# buckConverterRev3schematic.net
KiCad netlist of a schematic drawn in EAGLE
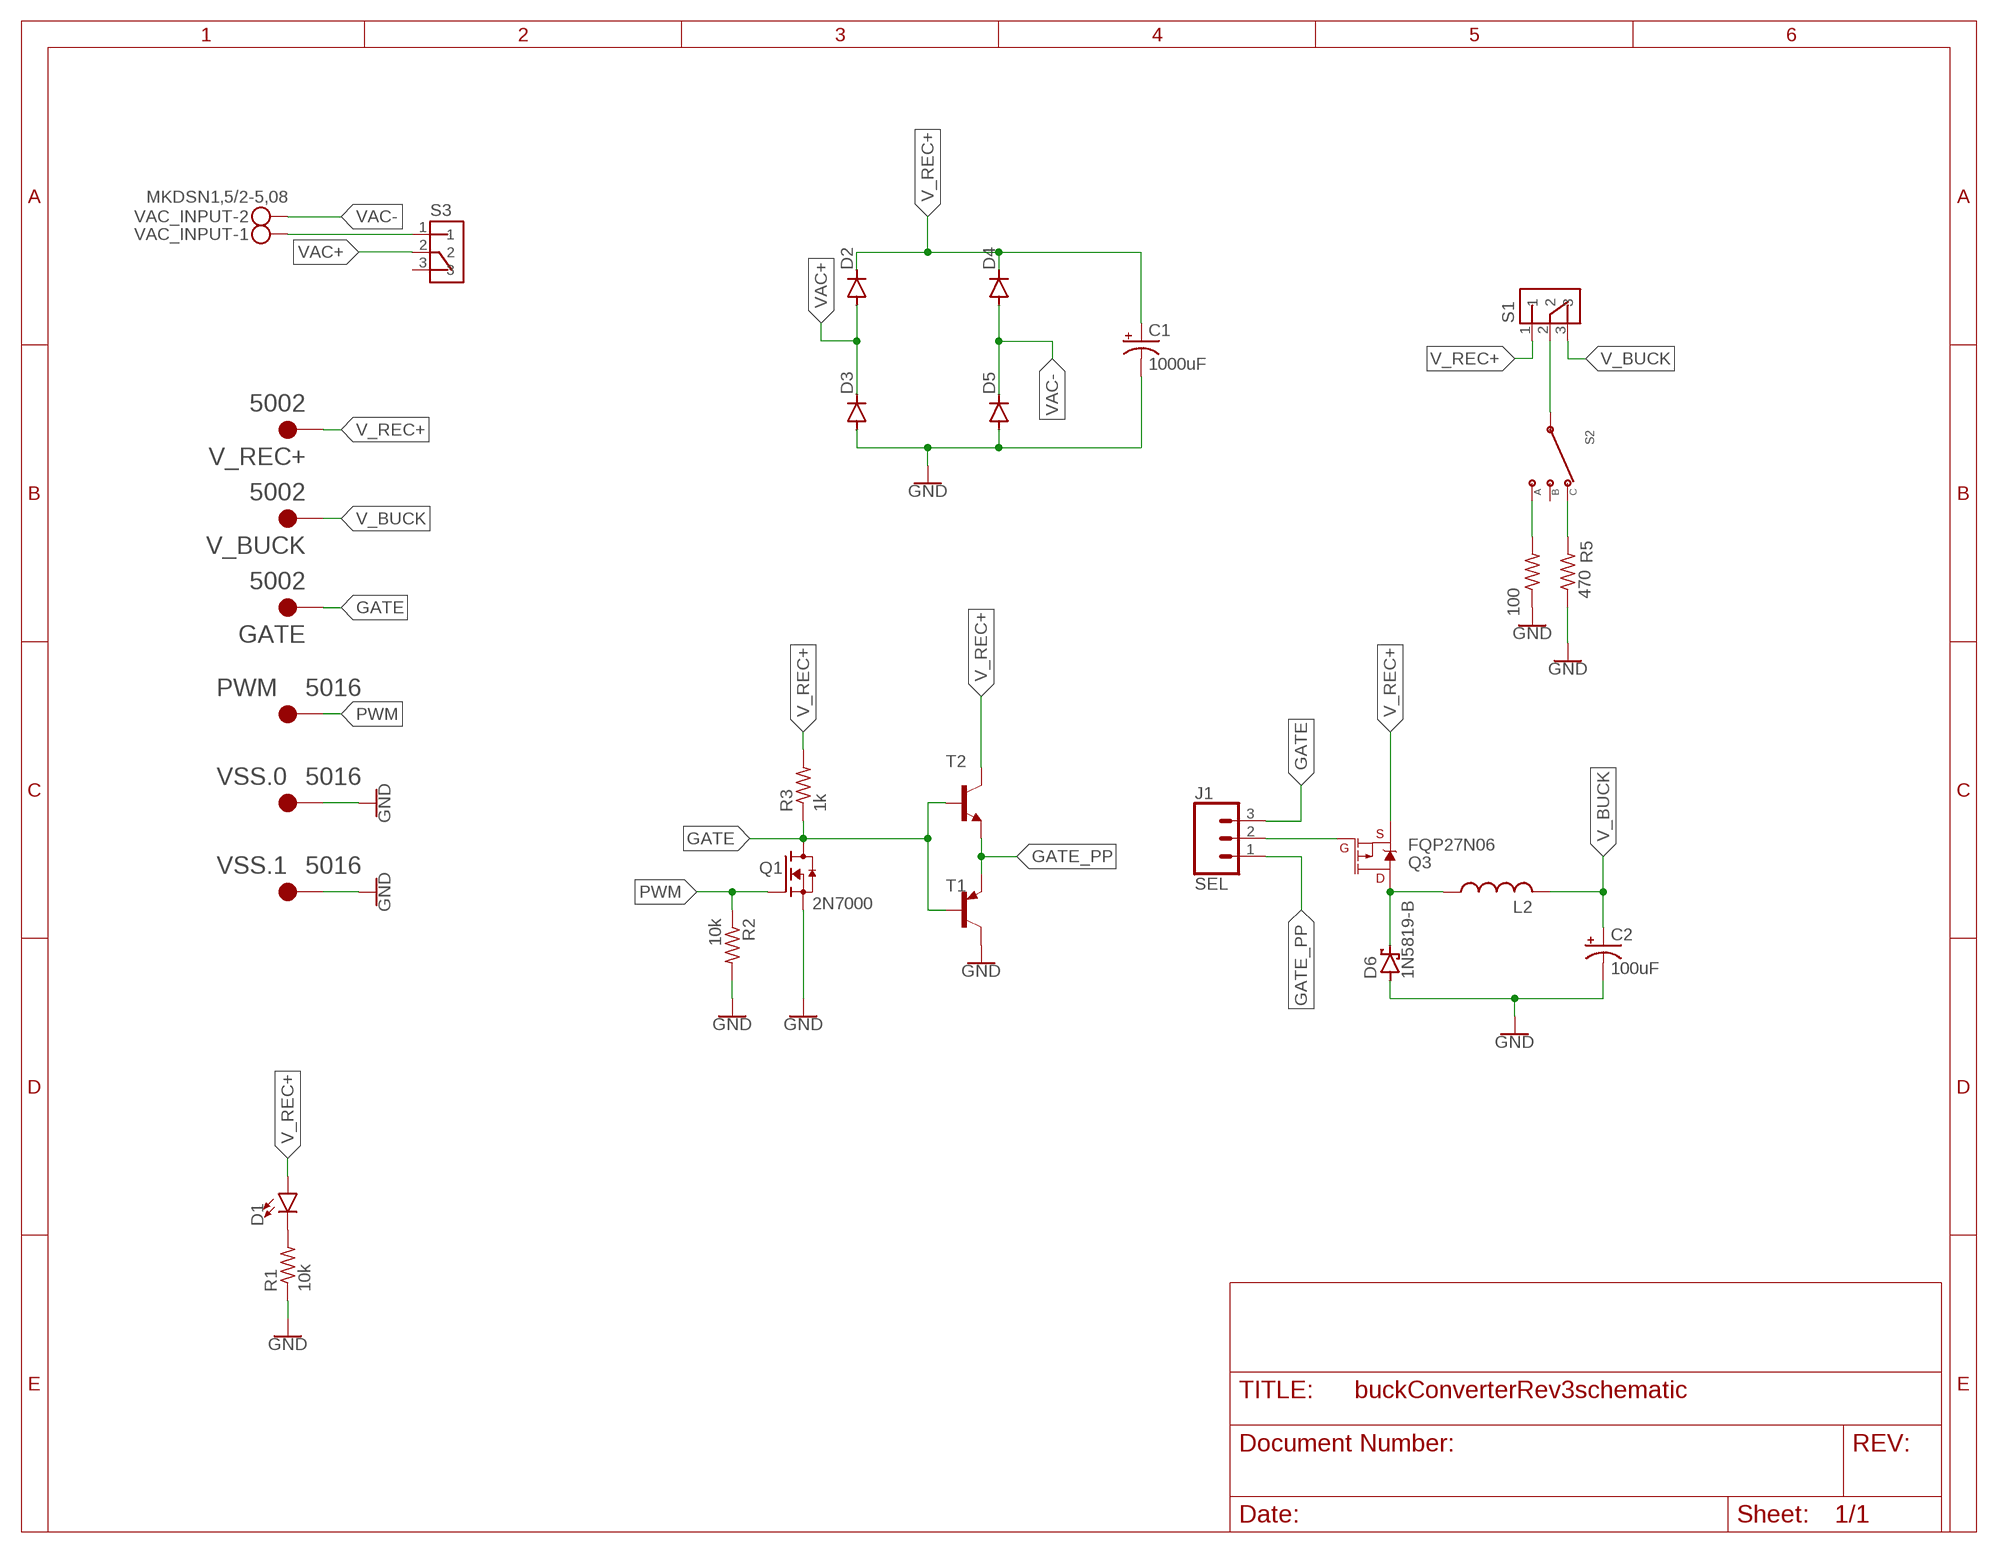
[diagram p0: schematic, sheet 1]

(export (version "E")
  (design (tool "Eeschema 10.0.6"))
  (components
    (comp (ref "C1")
      (value "1000uF")
      (footprint "eagle-import:SANYO-OSCON_F13")
      (libsource (lib "eagle-import") (part "CPOL-USSANYO_F13"))
    )
    (comp (ref "C2")
      (value "100uF")
      (footprint "eagle-import:SANYO-OSCON_C")
      (libsource (lib "eagle-import") (part "CPOL-USSANYO_C"))
    )
    (comp (ref "D1")
      (value "LED5MM")
      (footprint "eagle-import:LED_5MM")
      (libsource (lib "eagle-import") (part "LED5MM"))
    )
    (comp (ref "D2")
      (value "DIODE-DO41-7.6")
      (footprint "eagle-import:DO41-7.6")
      (libsource (lib "eagle-import") (part "DIODE-DO41-7.6"))
    )
    (comp (ref "D3")
      (value "DIODE-DO41-7.6")
      (footprint "eagle-import:DO41-7.6")
      (libsource (lib "eagle-import") (part "DIODE-DO41-7.6"))
    )
    (comp (ref "D4")
      (value "DIODE-DO41-7.6")
      (footprint "eagle-import:DO41-7.6")
      (libsource (lib "eagle-import") (part "DIODE-DO41-7.6"))
    )
    (comp (ref "D5")
      (value "DIODE-DO41-7.6")
      (footprint "eagle-import:DO41-7.6")
      (libsource (lib "eagle-import") (part "DIODE-DO41-7.6"))
    )
    (comp (ref "D6")
      (value "1N5819-B")
      (footprint "eagle-import:DO41-7.6")
      (libsource (lib "eagle-import") (part "1N5819-B"))
    )
    (comp (ref "GATE")
      (value "5002")
      (footprint "eagle-import:KEYSTONE_5002")
      (fields (field (name "MANUFACTURER") "Keystone"))
      (libsource (lib "eagle-import") (part "5002"))
    )
    (comp (ref "J1")
      (value "SEL")
      (footprint "eagle-import:1X03_LOCK_LONGPADS")
      (libsource (lib "eagle-import") (part "CONN_03LOCK_LONGPADS"))
    )
    (comp (ref "L2")
      (value "L-US6000-XXX-RC")
      (footprint "eagle-import:6000-XXXX-RC")
      (libsource (lib "eagle-import") (part "L-US6000-XXX-RC"))
    )
    (comp (ref "PWM")
      (value "5016")
      (footprint "eagle-import:KEYSTONE_5016")
      (fields (field (name "MANUFACTURER") "Keystone Electronics"))
      (libsource (lib "eagle-import") (part "5016"))
    )
    (comp (ref "Q1")
      (value "2N7000")
      (footprint "eagle-import:TO92254P458H750-3")
      (fields (field (name "MANUFACTURER") "Diotec Semiconductor"))
      (libsource (lib "eagle-import") (part "2N7000"))
    )
    (comp (ref "Q3")
      (value "FQP27N06")
      (footprint "eagle-import:TO220V")
      (libsource (lib "eagle-import") (part "MOSFET_PCH-NDP6020P"))
    )
    (comp (ref "R1")
      (value "10k")
      (footprint "eagle-import:0207_10")
      (libsource (lib "eagle-import") (part "R-US_0207/10"))
    )
    (comp (ref "R2")
      (value "10k")
      (footprint "eagle-import:0207_10")
      (libsource (lib "eagle-import") (part "R-US_0207/10"))
    )
    (comp (ref "R3")
      (value "1k")
      (footprint "eagle-import:0207_10")
      (libsource (lib "eagle-import") (part "R-US_0207/10"))
    )
    (comp (ref "R4")
      (value "100")
      (footprint "eagle-import:0617_22")
      (libsource (lib "eagle-import") (part "R-US_0617/22"))
    )
    (comp (ref "R5")
      (value "470")
      (footprint "eagle-import:0309_12")
      (libsource (lib "eagle-import") (part "R-US_0309/12"))
    )
    (comp (ref "S1")
      (value "OS102011MS2QN1")
      (footprint "eagle-import:SW_OS102011MS2QN1")
      (fields (field (name "MF") "C&K"))
      (libsource (lib "eagle-import") (part "OS102011MS2QN1"))
    )
    (comp (ref "S2")
      (value "OS103011MS8QP1")
      (footprint "eagle-import:OS102011MS8QP1")
      (fields (field (name "MF") "C&K"))
      (libsource (lib "eagle-import") (part "OS103011MS8QP1"))
    )
    (comp (ref "S3")
      (value "ON/OFF")
      (footprint "eagle-import:SW_OS102011MS2QN1")
      (fields (field (name "MF") "C&K") (field (name "MP") "OS102011MS2QN1"))
      (libsource (lib "eagle-import") (part "OS102011MS2QN1"))
    )
    (comp (ref "T1")
      (value "2N3906-PNP-TO92-EBC")
      (footprint "eagle-import:TO92-EBC")
      (libsource (lib "eagle-import") (part "-PNP-TO92-EBC2N3906"))
    )
    (comp (ref "T2")
      (value "2N3904-NPN-TO92-EBC")
      (footprint "eagle-import:TO92-EBC")
      (libsource (lib "eagle-import") (part "-NPN-TO92-EBC2N3904"))
    )
    (comp (ref "VAC_INPUT")
      (value "MKDSN1,5/2-5,08")
      (footprint "eagle-import:MKDSN1,5_2-5,08")
      (libsource (lib "eagle-import") (part "MKDSN1,5/2-5,08"))
    )
    (comp (ref "VSS.0")
      (value "5016")
      (footprint "eagle-import:KEYSTONE_5016")
      (fields (field (name "MANUFACTURER") "Keystone Electronics"))
      (libsource (lib "eagle-import") (part "5016"))
    )
    (comp (ref "VSS.1")
      (value "5016")
      (footprint "eagle-import:KEYSTONE_5016")
      (fields (field (name "MANUFACTURER") "Keystone Electronics"))
      (libsource (lib "eagle-import") (part "5016"))
    )
    (comp (ref "V_BUCK")
      (value "5002")
      (footprint "eagle-import:KEYSTONE_5002")
      (fields (field (name "MANUFACTURER") "Keystone"))
      (libsource (lib "eagle-import") (part "5002"))
    )
    (comp (ref "V_REC+")
      (value "5002")
      (footprint "eagle-import:KEYSTONE_5002")
      (fields (field (name "MANUFACTURER") "Keystone"))
      (libsource (lib "eagle-import") (part "5002"))
    )
  )
  (nets
    (net (code "1") (name "GATE") (class "Default")
      (node (ref "GATE") (pin "TP") (pinfunction "TP_TP") (pintype "passive"))
      (node (ref "J1") (pin "3") (pinfunction "3_3") (pintype "passive"))
      (node (ref "Q1") (pin "3") (pinfunction "D_3") (pintype "passive"))
      (node (ref "R3") (pin "1") (pinfunction "1_1") (pintype "passive"))
      (node (ref "T1") (pin "B") (pinfunction "B_B") (pintype "passive"))
      (node (ref "T2") (pin "B") (pinfunction "B_B") (pintype "passive"))
    )
    (net (code "2") (name "GATE_PP") (class "Default")
      (node (ref "J1") (pin "1") (pinfunction "1_1") (pintype "passive"))
      (node (ref "T1") (pin "E") (pinfunction "E_E") (pintype "passive"))
      (node (ref "T2") (pin "E") (pinfunction "E_E") (pintype "passive"))
    )
    (net (code "3") (name "GND") (class "Default")
      (node (ref "C1") (pin "-") (pinfunction "-_-") (pintype "passive"))
      (node (ref "C2") (pin "-") (pinfunction "-_-") (pintype "passive"))
      (node (ref "D3") (pin "A") (pinfunction "A_A") (pintype "passive"))
      (node (ref "D5") (pin "A") (pinfunction "A_A") (pintype "passive"))
      (node (ref "D6") (pin "A") (pinfunction "A_A") (pintype "passive"))
      (node (ref "Q1") (pin "1") (pinfunction "S_1") (pintype "passive"))
      (node (ref "R1") (pin "1") (pinfunction "1_1") (pintype "passive"))
      (node (ref "R2") (pin "2") (pinfunction "2_2") (pintype "passive"))
      (node (ref "R4") (pin "1") (pinfunction "1_1") (pintype "passive"))
      (node (ref "R5") (pin "1") (pinfunction "1_1") (pintype "passive"))
      (node (ref "T1") (pin "C") (pinfunction "C_C") (pintype "passive"))
      (node (ref "VSS.0") (pin "TP") (pinfunction "TP_TP") (pintype "passive"))
      (node (ref "VSS.1") (pin "TP") (pinfunction "TP_TP") (pintype "passive"))
    )
    (net (code "4") (name "Net-(D1-C)") (class "Default")
      (node (ref "D1") (pin "K") (pinfunction "C_K") (pintype "passive"))
      (node (ref "R1") (pin "2") (pinfunction "2_2") (pintype "passive"))
    )
    (net (code "5") (name "Net-(Q3-D)") (class "Default")
      (node (ref "D6") (pin "C") (pinfunction "C_C") (pintype "passive"))
      (node (ref "L2") (pin "1") (pinfunction "1_1") (pintype "passive"))
      (node (ref "Q3") (pin "2") (pinfunction "D_2") (pintype "bidirectional"))
    )
    (net (code "6") (name "Net-(Q3-G)") (class "Default")
      (node (ref "J1") (pin "2") (pinfunction "2_2") (pintype "passive"))
      (node (ref "Q3") (pin "1") (pinfunction "G_1") (pintype "bidirectional"))
    )
    (net (code "7") (name "Net-(R4-Pad2)") (class "Default")
      (node (ref "R4") (pin "2") (pinfunction "2_2") (pintype "passive"))
      (node (ref "S2") (pin "1") (pinfunction "1_1") (pintype "bidirectional"))
    )
    (net (code "8") (name "Net-(S2-3)") (class "Default")
      (node (ref "R5") (pin "2") (pinfunction "2_2") (pintype "passive"))
      (node (ref "S2") (pin "4") (pinfunction "3_4") (pintype "bidirectional"))
    )
    (net (code "9") (name "Net-(S2-C)") (class "Default")
      (node (ref "S1") (pin "2") (pinfunction "2_2") (pintype "passive"))
      (node (ref "S2") (pin "2") (pinfunction "C_2") (pintype "bidirectional"))
    )
    (net (code "10") (name "Net-(VAC_INPUTA-KL)") (class "Default")
      (node (ref "S3") (pin "1") (pinfunction "1_1") (pintype "passive"))
      (node (ref "VAC_INPUT") (pin "1") (pinfunction "KL_1") (pintype "passive"))
    )
    (net (code "11") (name "PWM") (class "Default")
      (node (ref "PWM") (pin "TP") (pinfunction "TP_TP") (pintype "passive"))
      (node (ref "Q1") (pin "2") (pinfunction "G_2") (pintype "passive"))
      (node (ref "R2") (pin "1") (pinfunction "1_1") (pintype "passive"))
    )
    (net (code "12") (name "VAC+") (class "Default")
      (node (ref "D2") (pin "A") (pinfunction "A_A") (pintype "passive"))
      (node (ref "D3") (pin "C") (pinfunction "C_C") (pintype "passive"))
      (node (ref "S3") (pin "2") (pinfunction "2_2") (pintype "passive"))
    )
    (net (code "13") (name "VAC-") (class "Default")
      (node (ref "D4") (pin "A") (pinfunction "A_A") (pintype "passive"))
      (node (ref "D5") (pin "C") (pinfunction "C_C") (pintype "passive"))
      (node (ref "VAC_INPUT") (pin "2") (pinfunction "KL_2") (pintype "passive"))
    )
    (net (code "14") (name "V_BUCK") (class "Default")
      (node (ref "C2") (pin "+") (pinfunction "+_+") (pintype "passive"))
      (node (ref "L2") (pin "2") (pinfunction "2_2") (pintype "passive"))
      (node (ref "S1") (pin "3") (pinfunction "3_3") (pintype "passive"))
      (node (ref "V_BUCK") (pin "TP") (pinfunction "TP_TP") (pintype "passive"))
    )
    (net (code "15") (name "V_REC+") (class "Default")
      (node (ref "C1") (pin "+") (pinfunction "+_+") (pintype "passive"))
      (node (ref "D1") (pin "A") (pinfunction "A_A") (pintype "passive"))
      (node (ref "D2") (pin "C") (pinfunction "C_C") (pintype "passive"))
      (node (ref "D4") (pin "C") (pinfunction "C_C") (pintype "passive"))
      (node (ref "Q3") (pin "3") (pinfunction "S_3") (pintype "bidirectional"))
      (node (ref "R3") (pin "2") (pinfunction "2_2") (pintype "passive"))
      (node (ref "S1") (pin "1") (pinfunction "1_1") (pintype "passive"))
      (node (ref "T2") (pin "C") (pinfunction "C_C") (pintype "passive"))
      (node (ref "V_REC+") (pin "TP") (pinfunction "TP_TP") (pintype "passive"))
    )
    (net (code "16") (name "unconnected-(S2-2-Pad3)") (class "Default")
      (node (ref "S2") (pin "3") (pinfunction "2_3") (pintype "bidirectional"))
    )
    (net (code "17") (name "unconnected-(S3-Pad3)") (class "Default")
      (node (ref "S3") (pin "3") (pinfunction "3_3") (pintype "passive"))
    )
  )
)
